# USB_JoystickKeyboarMouse.net
KiCad netlist of a schematic drawn in EAGLE
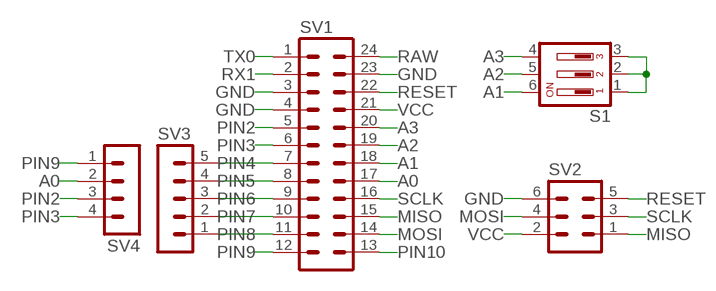
[diagram p0: schematic, sheet 1]

(export (version "E")
  (design (tool "Eeschema 10.0.6"))
  (components
    (comp (ref "S1")
      (value "DIP03YL")
      (footprint "eagle-import:DIP03YL")
      (libsource (lib "eagle-import") (part "DIP03YL"))
    )
    (comp (ref "SV1")
      (value "IC24P")
      (footprint "eagle-import:IC24P")
      (libsource (lib "eagle-import") (part "IC24P"))
    )
    (comp (ref "SV2")
      (value "MA03-2")
      (footprint "eagle-import:MA03-2")
      (libsource (lib "eagle-import") (part "MA03-2"))
    )
    (comp (ref "SV3")
      (value "MA05-1")
      (footprint "eagle-import:MA05-1")
      (libsource (lib "eagle-import") (part "MA05-1"))
    )
    (comp (ref "SV4")
      (value "MA04-1")
      (footprint "eagle-import:MA04-1")
      (libsource (lib "eagle-import") (part "MA04-1"))
    )
  )
  (nets
    (net (code "1") (name "/A0") (class "Default")
      (node (ref "SV1") (pin "17") (pinfunction "17_17") (pintype "passive"))
      (node (ref "SV4") (pin "2") (pinfunction "2_2") (pintype "passive"))
    )
    (net (code "2") (name "/A1") (class "Default")
      (node (ref "S1") (pin "6") (pinfunction "6_6") (pintype "passive"))
      (node (ref "SV1") (pin "18") (pinfunction "18_18") (pintype "passive"))
    )
    (net (code "3") (name "/A2") (class "Default")
      (node (ref "S1") (pin "5") (pinfunction "5_5") (pintype "passive"))
      (node (ref "SV1") (pin "19") (pinfunction "19_19") (pintype "passive"))
    )
    (net (code "4") (name "/A3") (class "Default")
      (node (ref "S1") (pin "4") (pinfunction "4_4") (pintype "passive"))
      (node (ref "SV1") (pin "20") (pinfunction "20_20") (pintype "passive"))
    )
    (net (code "5") (name "/GND") (class "Default")
      (node (ref "S1") (pin "1") (pinfunction "1_1") (pintype "passive"))
      (node (ref "S1") (pin "2") (pinfunction "2_2") (pintype "passive"))
      (node (ref "S1") (pin "3") (pinfunction "3_3") (pintype "passive"))
      (node (ref "SV1") (pin "23") (pinfunction "23_23") (pintype "passive"))
      (node (ref "SV1") (pin "3") (pinfunction "3_3") (pintype "passive"))
      (node (ref "SV1") (pin "4") (pinfunction "4_4") (pintype "passive"))
      (node (ref "SV2") (pin "6") (pinfunction "6_6") (pintype "passive"))
    )
    (net (code "6") (name "/MISO") (class "Default")
      (node (ref "SV1") (pin "15") (pinfunction "15_15") (pintype "passive"))
      (node (ref "SV2") (pin "1") (pinfunction "1_1") (pintype "passive"))
    )
    (net (code "7") (name "/MOSI") (class "Default")
      (node (ref "SV1") (pin "14") (pinfunction "14_14") (pintype "passive"))
      (node (ref "SV2") (pin "4") (pinfunction "4_4") (pintype "passive"))
    )
    (net (code "8") (name "/PIN2") (class "Default")
      (node (ref "SV1") (pin "5") (pinfunction "5_5") (pintype "passive"))
      (node (ref "SV4") (pin "3") (pinfunction "3_3") (pintype "passive"))
    )
    (net (code "9") (name "/PIN3") (class "Default")
      (node (ref "SV1") (pin "6") (pinfunction "6_6") (pintype "passive"))
      (node (ref "SV4") (pin "4") (pinfunction "4_4") (pintype "passive"))
    )
    (net (code "10") (name "/PIN4") (class "Default")
      (node (ref "SV1") (pin "7") (pinfunction "7_7") (pintype "passive"))
      (node (ref "SV3") (pin "5") (pinfunction "5_5") (pintype "passive"))
    )
    (net (code "11") (name "/PIN5") (class "Default")
      (node (ref "SV1") (pin "8") (pinfunction "8_8") (pintype "passive"))
      (node (ref "SV3") (pin "4") (pinfunction "4_4") (pintype "passive"))
    )
    (net (code "12") (name "/PIN6") (class "Default")
      (node (ref "SV1") (pin "9") (pinfunction "9_9") (pintype "passive"))
      (node (ref "SV3") (pin "3") (pinfunction "3_3") (pintype "passive"))
    )
    (net (code "13") (name "/PIN7") (class "Default")
      (node (ref "SV1") (pin "10") (pinfunction "10_10") (pintype "passive"))
      (node (ref "SV3") (pin "2") (pinfunction "2_2") (pintype "passive"))
    )
    (net (code "14") (name "/PIN8") (class "Default")
      (node (ref "SV1") (pin "11") (pinfunction "11_11") (pintype "passive"))
      (node (ref "SV3") (pin "1") (pinfunction "1_1") (pintype "passive"))
    )
    (net (code "15") (name "/PIN9") (class "Default")
      (node (ref "SV1") (pin "12") (pinfunction "12_12") (pintype "passive"))
      (node (ref "SV4") (pin "1") (pinfunction "1_1") (pintype "passive"))
    )
    (net (code "16") (name "/PIN10") (class "Default")
      (node (ref "SV1") (pin "13") (pinfunction "13_13") (pintype "passive"))
    )
    (net (code "17") (name "/RAW") (class "Default")
      (node (ref "SV1") (pin "24") (pinfunction "24_24") (pintype "passive"))
    )
    (net (code "18") (name "/RESET") (class "Default")
      (node (ref "SV1") (pin "22") (pinfunction "22_22") (pintype "passive"))
      (node (ref "SV2") (pin "5") (pinfunction "5_5") (pintype "passive"))
    )
    (net (code "19") (name "/RX1") (class "Default")
      (node (ref "SV1") (pin "2") (pinfunction "2_2") (pintype "passive"))
    )
    (net (code "20") (name "/SCLK") (class "Default")
      (node (ref "SV1") (pin "16") (pinfunction "16_16") (pintype "passive"))
      (node (ref "SV2") (pin "3") (pinfunction "3_3") (pintype "passive"))
    )
    (net (code "21") (name "/TX0") (class "Default")
      (node (ref "SV1") (pin "1") (pinfunction "1_1") (pintype "passive"))
    )
    (net (code "22") (name "/VCC") (class "Default")
      (node (ref "SV1") (pin "21") (pinfunction "21_21") (pintype "passive"))
      (node (ref "SV2") (pin "2") (pinfunction "2_2") (pintype "passive"))
    )
  )
)
